# Sheet1.net
KiCad netlist of a schematic drawn in Altium Designer
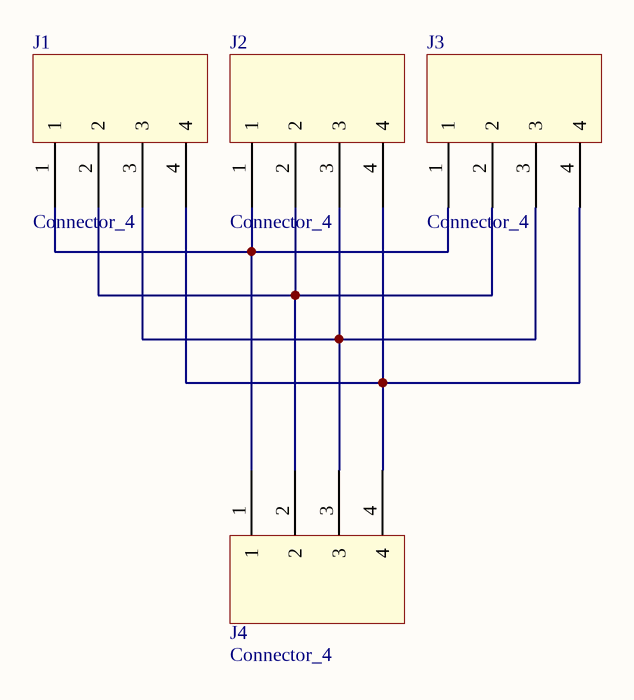
[diagram p0: Sheet1.SchDoc]

(export (version "E")
  (design (tool "Eeschema 10.0.6"))
  (components
    (comp (ref "J1")
      (value "Connector_4")
      (footprint "PTSM 0,5/ 4-HHI-2,5-THR WH R32")
      (libsource (lib "PTSM") (part "Connector_4"))
    )
    (comp (ref "J2")
      (value "Connector_4")
      (footprint "PTSM 0,5/ 4-HHI-2,5-THR WH R32")
      (libsource (lib "PTSM") (part "Connector_4"))
    )
    (comp (ref "J3")
      (value "Connector_4")
      (footprint "PTSM 0,5/ 4-HHI-2,5-THR WH R32")
      (libsource (lib "PTSM") (part "Connector_4"))
    )
    (comp (ref "J4")
      (value "Connector_4")
      (footprint "PTSM 0,5/ 4-2,5-H THR WH R32")
      (libsource (lib "") (part "Connector_4_1"))
    )
  )
  (nets
    (net (code "1") (name "Net-(J1-Pad1)") (class "Default")
      (node (ref "J1") (pin "1") (pinfunction "1_1") (pintype "passive"))
      (node (ref "J2") (pin "1") (pinfunction "1_1") (pintype "passive"))
      (node (ref "J3") (pin "1") (pinfunction "1_1") (pintype "passive"))
      (node (ref "J4") (pin "1") (pinfunction "1_1") (pintype "passive"))
    )
    (net (code "2") (name "Net-(J1-Pad2)") (class "Default")
      (node (ref "J1") (pin "2") (pinfunction "2_2") (pintype "passive"))
      (node (ref "J2") (pin "2") (pinfunction "2_2") (pintype "passive"))
      (node (ref "J3") (pin "2") (pinfunction "2_2") (pintype "passive"))
      (node (ref "J4") (pin "2") (pinfunction "2_2") (pintype "passive"))
    )
    (net (code "3") (name "Net-(J1-Pad3)") (class "Default")
      (node (ref "J1") (pin "3") (pinfunction "3_3") (pintype "passive"))
      (node (ref "J2") (pin "3") (pinfunction "3_3") (pintype "passive"))
      (node (ref "J3") (pin "3") (pinfunction "3_3") (pintype "passive"))
      (node (ref "J4") (pin "3") (pinfunction "3_3") (pintype "passive"))
    )
    (net (code "4") (name "Net-(J1-Pad4)") (class "Default")
      (node (ref "J1") (pin "4") (pinfunction "4_4") (pintype "passive"))
      (node (ref "J2") (pin "4") (pinfunction "4_4") (pintype "passive"))
      (node (ref "J3") (pin "4") (pinfunction "4_4") (pintype "passive"))
      (node (ref "J4") (pin "4") (pinfunction "4_4") (pintype "passive"))
    )
  )
)
